# STM32F103RCT6.net
KiCad netlist of a schematic drawn in Altium Designer
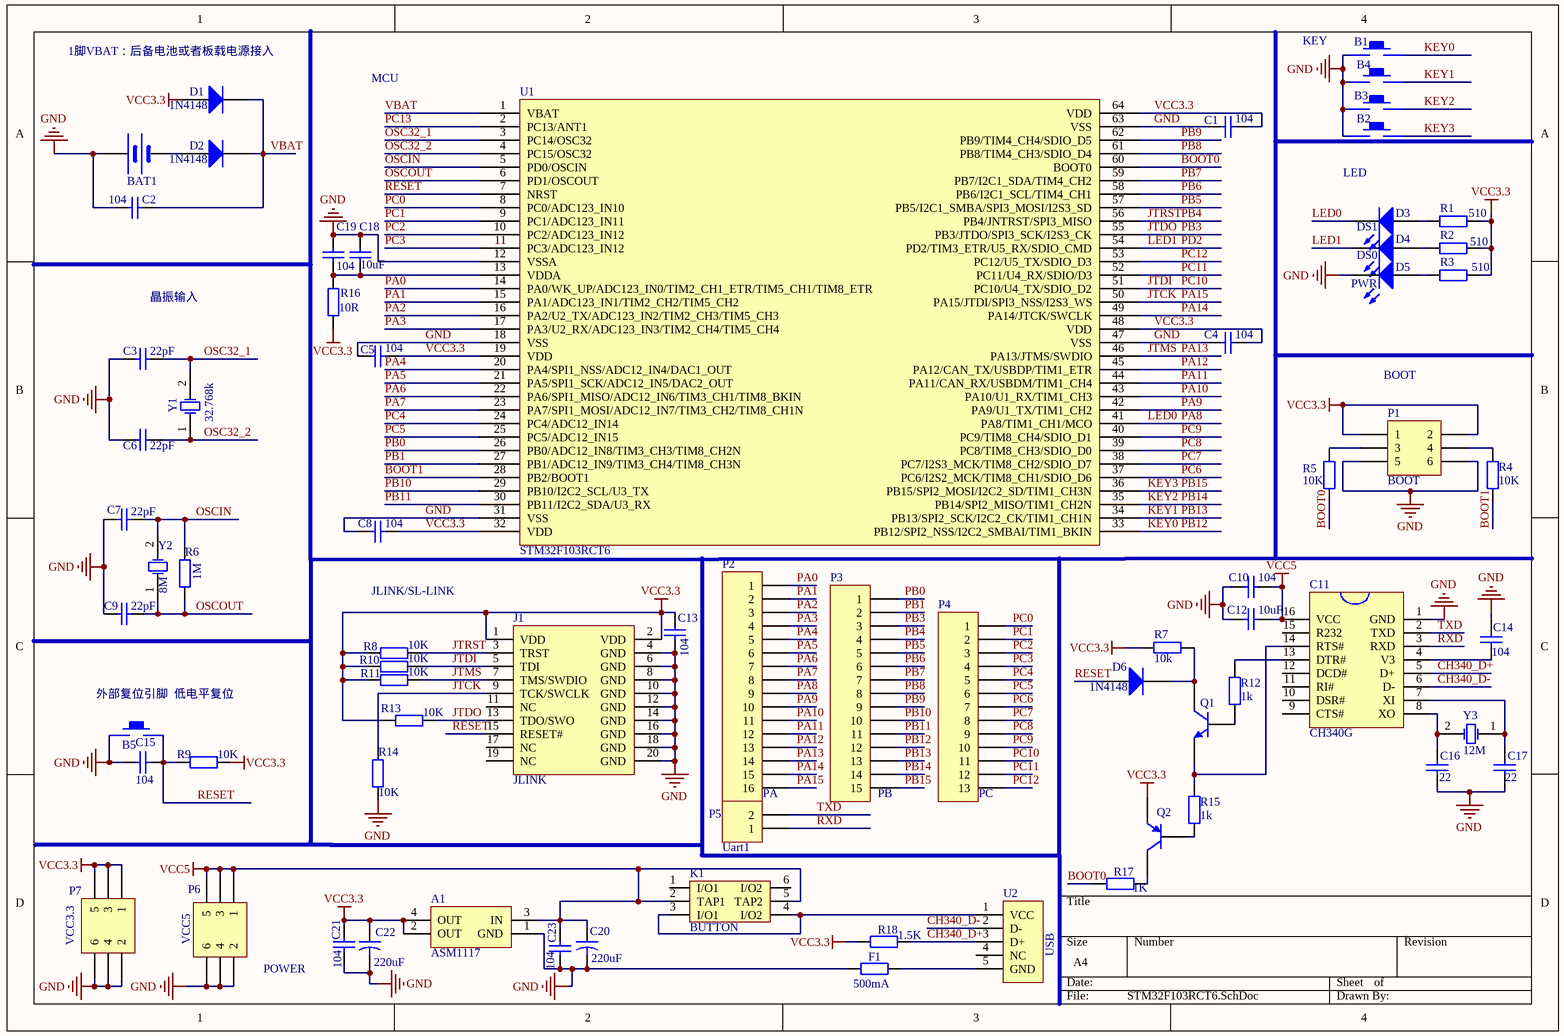
[diagram p0: STM32F103RCT6.SchDoc]

(export (version "E")
  (design (tool "Eeschema 10.0.6"))
  (components
    (comp (ref "A1") (value "ASM1117") (footprint "AMS1117") (libsource (lib "STM32F103") (part "AMS117")))
    (comp (ref "B1") (value "Button") (footprint "KEY_M") (libsource (lib "STM32F103") (part "Button")))
    (comp (ref "B2") (value "Button") (footprint "KEY_M") (libsource (lib "STM32F103") (part "Button")))
    (comp (ref "B3") (value "Button") (footprint "KEY_M") (libsource (lib "STM32F103") (part "Button")))
    (comp (ref "B4") (value "Button") (footprint "KEY_M") (libsource (lib "STM32F103") (part "Button")))
    (comp (ref "B5") (value "Button") (footprint "KEY_M") (libsource (lib "STM32F103") (part "Button")))
    (comp (ref "BAT1") (value "BATT") (footprint "BATM") (libsource (lib "MiniSTM32 V3.0封装库") (part "BAT")))
    (comp (ref "C1")
      (value "104")
      (footprint "0603P")
      (description "Capacitor")
      (fields (field (name "PUBLISHER") "Altium Limited"))
      (libsource (lib "Miscellaneous Devices") (part "Cap"))
    )
    (comp (ref "C2")
      (value "104")
      (footprint "0603P")
      (description "Capacitor")
      (fields (field (name "PUBLISHER") "Altium Limited"))
      (libsource (lib "Miscellaneous Devices") (part "Cap"))
    )
    (comp (ref "C3")
      (value "22pF")
      (footprint "0603P")
      (description "Capacitor")
      (fields (field (name "PUBLISHER") "Altium Limited"))
      (libsource (lib "Miscellaneous Devices") (part "Cap"))
    )
    (comp (ref "C4")
      (value "104")
      (footprint "0603P")
      (description "Capacitor")
      (fields (field (name "PUBLISHER") "Altium Limited"))
      (libsource (lib "Miscellaneous Devices") (part "Cap"))
    )
    (comp (ref "C5")
      (value "104")
      (footprint "0603P")
      (description "Capacitor")
      (fields (field (name "PUBLISHER") "Altium Limited"))
      (libsource (lib "Miscellaneous Devices") (part "Cap"))
    )
    (comp (ref "C6")
      (value "22pF")
      (footprint "0603P")
      (description "Capacitor")
      (fields (field (name "PUBLISHER") "Altium Limited"))
      (libsource (lib "Miscellaneous Devices") (part "Cap"))
    )
    (comp (ref "C7")
      (value "22pF")
      (footprint "0603P")
      (description "Capacitor")
      (fields (field (name "PUBLISHER") "Altium Limited"))
      (libsource (lib "Miscellaneous Devices") (part "Cap"))
    )
    (comp (ref "C8")
      (value "104")
      (footprint "0603P")
      (description "Capacitor")
      (fields (field (name "PUBLISHER") "Altium Limited"))
      (libsource (lib "Miscellaneous Devices") (part "Cap"))
    )
    (comp (ref "C9")
      (value "22pF")
      (footprint "0603P")
      (description "Capacitor")
      (fields (field (name "PUBLISHER") "Altium Limited"))
      (libsource (lib "Miscellaneous Devices") (part "Cap"))
    )
    (comp (ref "C10")
      (value "104")
      (footprint "0603P")
      (description "Capacitor")
      (fields (field (name "PUBLISHER") "Altium Limited"))
      (libsource (lib "Miscellaneous Devices") (part "Cap"))
    )
    (comp (ref "C11") (value "CH340G") (footprint "SOP16M") (libsource (lib "STM32F103") (part "CH340G")))
    (comp (ref "C12")
      (value "10uF")
      (footprint "0805")
      (description "Capacitor")
      (fields (field (name "PUBLISHER") "Altium Limited"))
      (libsource (lib "Miscellaneous Devices") (part "Cap"))
    )
    (comp (ref "C13")
      (value "104")
      (footprint "0603P")
      (description "Capacitor")
      (fields (field (name "PUBLISHER") "Altium Limited"))
      (libsource (lib "Miscellaneous Devices") (part "Cap"))
    )
    (comp (ref "C14")
      (value "104")
      (footprint "0603P")
      (description "Capacitor")
      (fields (field (name "PUBLISHER") "Altium Limited"))
      (libsource (lib "Miscellaneous Devices") (part "Cap"))
    )
    (comp (ref "C15")
      (value "104")
      (footprint "0603P")
      (description "Capacitor")
      (fields (field (name "PUBLISHER") "Altium Limited"))
      (libsource (lib "Miscellaneous Devices") (part "Cap"))
    )
    (comp (ref "C16")
      (value "22")
      (footprint "0603P")
      (description "Capacitor")
      (fields (field (name "PUBLISHER") "Altium Limited"))
      (libsource (lib "Miscellaneous Devices") (part "Cap"))
    )
    (comp (ref "C17")
      (value "22")
      (footprint "0603P")
      (description "Capacitor")
      (fields (field (name "PUBLISHER") "Altium Limited"))
      (libsource (lib "Miscellaneous Devices") (part "Cap"))
    )
    (comp (ref "C18")
      (value "10uF")
      (footprint "0805")
      (description "Capacitor")
      (fields (field (name "PUBLISHER") "Altium Limited"))
      (libsource (lib "Miscellaneous Devices") (part "Cap"))
    )
    (comp (ref "C19")
      (value "104")
      (footprint "0603P")
      (description "Capacitor")
      (fields (field (name "PUBLISHER") "Altium Limited"))
      (libsource (lib "Miscellaneous Devices") (part "Cap"))
    )
    (comp (ref "C20")
      (value "220uF")
      (footprint "CC6.56.5")
      (description "Capacitor")
      (fields (field (name "Comment") "Cap2") (field (name "PUBLISHER") "Altium Limited"))
      (libsource (lib "Miscellaneous Devices") (part "Cap2"))
    )
    (comp (ref "C21")
      (value "104")
      (footprint "0603P")
      (description "Capacitor")
      (fields (field (name "PUBLISHER") "Altium Limited"))
      (libsource (lib "Miscellaneous Devices") (part "Cap"))
    )
    (comp (ref "C22")
      (value "220uF")
      (footprint "CC6.56.5")
      (description "Capacitor")
      (fields (field (name "Comment") "Cap2") (field (name "PUBLISHER") "Altium Limited"))
      (libsource (lib "Miscellaneous Devices") (part "Cap2"))
    )
    (comp (ref "C23")
      (value "104")
      (footprint "0603P")
      (description "Capacitor")
      (fields (field (name "PUBLISHER") "Altium Limited"))
      (libsource (lib "Miscellaneous Devices") (part "Cap"))
    )
    (comp (ref "D1")
      (value "1N4148")
      (footprint "DIODE_SOP")
      (fields (field (name "PUBLISHER") "Altium Limited"))
      (libsource (lib "STM32F103") (part "LED"))
    )
    (comp (ref "D2")
      (value "1N4148")
      (footprint "DIODE_SOP")
      (fields (field (name "PUBLISHER") "Altium Limited"))
      (libsource (lib "STM32F103") (part "LED"))
    )
    (comp (ref "D3")
      (value "DS1")
      (footprint "DIODE_SOP")
      (description "Typical BLUE SiC LED")
      (fields (field (name "PUBLISHER") "Altium Limited"))
      (libsource (lib "Miscellaneous Devices") (part "LED3"))
    )
    (comp (ref "D4")
      (value "DS0")
      (footprint "DIODE_SOP")
      (description "Typical BLUE SiC LED")
      (fields (field (name "PUBLISHER") "Altium Limited"))
      (libsource (lib "Miscellaneous Devices") (part "LED3"))
    )
    (comp (ref "D5")
      (value "PWR")
      (footprint "DIODE_SOP")
      (description "Typical BLUE SiC LED")
      (fields (field (name "PUBLISHER") "Altium Limited"))
      (libsource (lib "Miscellaneous Devices") (part "LED3"))
    )
    (comp (ref "D6")
      (value "1N4148")
      (footprint "DIODE_SOP")
      (fields (field (name "PUBLISHER") "Altium Limited"))
      (libsource (lib "STM32F103") (part "LED"))
    )
    (comp (ref "F1")
      (value "500mA")
      (footprint "0805")
      (description "Resistor")
      (fields (field (name "PUBLISHER") "Altium Limited"))
      (libsource (lib "") (part "Res2_1"))
    )
    (comp (ref "J1")
      (value "JLINK")
      (footprint "JTAG_20")
      (fields (field (name "PUBLISHER") "Altium Limited"))
      (libsource (lib "STM32F103") (part "JLINK2X10"))
    )
    (comp (ref "K1")
      (value "BUTTON")
      (footprint "BTN8.5*8.5")
      (libsource (lib "MiniSTM32 V3.0封装库") (part "BUTTON"))
    )
    (comp (ref "P1")
      (value "BOOT")
      (footprint "HDR2X3")
      (description "Header, 3-Pin, Dual row")
      (fields (field (name "PUBLISHER") "Altium Limited"))
      (libsource (lib "Miscellaneous Connectors") (part "Header 3X2"))
    )
    (comp (ref "P2")
      (value "PA")
      (footprint "HDR1X16")
      (description "Header, 16-Pin")
      (fields (field (name "PUBLISHER") "Altium Limited"))
      (libsource (lib "Miscellaneous Connectors") (part "Header 16"))
    )
    (comp (ref "P3")
      (value "PB")
      (footprint "HDR1X15")
      (description "Header, 15-Pin")
      (fields (field (name "PUBLISHER") "Altium Limited"))
      (libsource (lib "Miscellaneous Connectors") (part "Header 15"))
    )
    (comp (ref "P4")
      (value "PC")
      (footprint "HDR1X13")
      (description "Header, 13-Pin")
      (fields (field (name "PUBLISHER") "Altium Limited"))
      (libsource (lib "Miscellaneous Connectors") (part "Header 13"))
    )
    (comp (ref "P5")
      (value "Uart1")
      (footprint "HDR1X2")
      (description "Header, 2-Pin")
      (fields (field (name "PUBLISHER") "Altium Limited"))
      (libsource (lib "Miscellaneous Connectors") (part "Header 2"))
    )
    (comp (ref "P6")
      (value "VCC5")
      (footprint "HDR2X3")
      (description "Header, 3-Pin, Dual row")
      (fields (field (name "PUBLISHER") "Altium Limited"))
      (libsource (lib "") (part "Header 3X2_1"))
    )
    (comp (ref "P7")
      (value "VCC3.3")
      (footprint "HDR2X3")
      (description "Header, 3-Pin, Dual row")
      (fields (field (name "PUBLISHER") "Altium Limited"))
      (libsource (lib "") (part "Header 3X2_1"))
    )
    (comp (ref "Q1")
      (value "2N3904")
      (footprint "SOT-23R")
      (description "NPN General Purpose Amplifier")
      (fields (field (name "PUBLISHER") "Altium Limited"))
      (libsource (lib "Miscellaneous Devices") (part "2N3904"))
    )
    (comp (ref "Q2")
      (value "2N3906")
      (footprint "SOT-23R")
      (description "PNP General Purpose Amplifier")
      (fields (field (name "PUBLISHER") "Altium Limited"))
      (libsource (lib "Miscellaneous Devices") (part "2N3906"))
    )
    (comp (ref "R1")
      (value "510")
      (footprint "0603P")
      (description "Resistor")
      (fields (field (name "Comment") "Res2") (field (name "PUBLISHER") "Altium Limited"))
      (libsource (lib "") (part "Res2_3"))
    )
    (comp (ref "R2")
      (value "510")
      (footprint "0603P")
      (description "Resistor")
      (fields (field (name "Comment") "Res2") (field (name "PUBLISHER") "Altium Limited"))
      (libsource (lib "") (part "Res2_3"))
    )
    (comp (ref "R3")
      (value "510")
      (footprint "0603P")
      (description "Resistor")
      (fields (field (name "Comment") "Res2") (field (name "PUBLISHER") "Altium Limited"))
      (libsource (lib "") (part "Res2_3"))
    )
    (comp (ref "R4")
      (value "10K")
      (footprint "0603P")
      (description "Resistor")
      (fields (field (name "Comment") "Res2") (field (name "PUBLISHER") "Altium Limited"))
      (libsource (lib "Miscellaneous Devices") (part "Res2"))
    )
    (comp (ref "R5")
      (value "10K")
      (footprint "0603P")
      (description "Resistor")
      (fields (field (name "Comment") "Res2") (field (name "PUBLISHER") "Altium Limited"))
      (libsource (lib "Miscellaneous Devices") (part "Res2"))
    )
    (comp (ref "R6")
      (value "1M")
      (footprint "0603P")
      (description "Resistor")
      (fields (field (name "Comment") "Res2") (field (name "PUBLISHER") "Altium Limited"))
      (libsource (lib "Miscellaneous Devices") (part "Res2"))
    )
    (comp (ref "R7")
      (value "10k")
      (footprint "0603P")
      (description "Resistor")
      (fields (field (name "Comment") "Res2") (field (name "PUBLISHER") "Altium Limited"))
      (libsource (lib "") (part "Res2_1"))
    )
    (comp (ref "R8")
      (value "10K")
      (footprint "0603P")
      (description "Resistor")
      (fields (field (name "Comment") "Res2") (field (name "PUBLISHER") "Altium Limited"))
      (libsource (lib "") (part "Res2_1"))
    )
    (comp (ref "R9")
      (value "10K")
      (footprint "0603P")
      (description "Resistor")
      (fields (field (name "Comment") "Res2") (field (name "PUBLISHER") "Altium Limited"))
      (libsource (lib "") (part "Res2_1"))
    )
    (comp (ref "R10")
      (value "10K")
      (footprint "0603P")
      (description "Resistor")
      (fields (field (name "Comment") "Res2") (field (name "PUBLISHER") "Altium Limited"))
      (libsource (lib "") (part "Res2_1"))
    )
    (comp (ref "R11")
      (value "10K")
      (footprint "0603P")
      (description "Resistor")
      (fields (field (name "Comment") "Res2") (field (name "PUBLISHER") "Altium Limited"))
      (libsource (lib "") (part "Res2_1"))
    )
    (comp (ref "R12")
      (value "1k")
      (footprint "0603P")
      (description "Resistor")
      (fields (field (name "Comment") "Res2") (field (name "PUBLISHER") "Altium Limited"))
      (libsource (lib "Miscellaneous Devices") (part "Res2"))
    )
    (comp (ref "R13")
      (value "10K")
      (footprint "0603P")
      (description "Resistor")
      (fields (field (name "Comment") "Res2") (field (name "PUBLISHER") "Altium Limited"))
      (libsource (lib "") (part "Res2_1"))
    )
    (comp (ref "R14")
      (value "10K")
      (footprint "0603P")
      (description "Resistor")
      (fields (field (name "Comment") "Res2") (field (name "PUBLISHER") "Altium Limited"))
      (libsource (lib "Miscellaneous Devices") (part "Res2"))
    )
    (comp (ref "R15")
      (value "1k")
      (footprint "0603P")
      (description "Resistor")
      (fields (field (name "Comment") "Res2") (field (name "PUBLISHER") "Altium Limited"))
      (libsource (lib "") (part "Res2_2"))
    )
    (comp (ref "R16")
      (value "10R")
      (footprint "0603P")
      (description "Resistor")
      (fields (field (name "Comment") "Res2") (field (name "PUBLISHER") "Altium Limited"))
      (libsource (lib "") (part "Res2_2"))
    )
    (comp (ref "R17")
      (value "1K")
      (footprint "0603P")
      (description "Resistor")
      (fields (field (name "Comment") "Res2") (field (name "PUBLISHER") "Altium Limited"))
      (libsource (lib "") (part "Res2_1"))
    )
    (comp (ref "R18")
      (value "1.5K")
      (footprint "0603P")
      (description "Resistor")
      (fields (field (name "Comment") "Res2") (field (name "PUBLISHER") "Altium Limited"))
      (libsource (lib "") (part "Res2_1"))
    )
    (comp (ref "U1")
      (value "STM32F103RCT6")
      (footprint "LQFP64")
      (libsource (lib "STM32F103") (part "STM32F103RCT6_64Pin"))
    )
    (comp (ref "U2") (value "USB") (footprint "USB/SM0.8-6H5") (libsource (lib "STM32F103") (part "USB")))
    (comp (ref "Y1")
      (value "32.768k")
      (footprint "XTAL32")
      (description "Crystal Oscillator")
      (fields (field (name "PUBLISHER") "Altium Limited"))
      (libsource (lib "Miscellaneous Devices") (part "XTAL"))
    )
    (comp (ref "Y2")
      (value "8M")
      (footprint "XTAL_US")
      (description "Crystal Oscillator")
      (fields (field (name "PUBLISHER") "Altium Limited"))
      (libsource (lib "Miscellaneous Devices") (part "XTAL"))
    )
    (comp (ref "Y3")
      (value "12M")
      (footprint "XTAL_US")
      (description "Crystal Oscillator")
      (fields (field (name "PUBLISHER") "Altium Limited"))
      (libsource (lib "Miscellaneous Devices") (part "XTAL"))
    )
  )
  (nets
    (net (code "1") (name "/BOOT0") (class "Default")
      (node (ref "R17") (pin "1") (pinfunction "1_1") (pintype "passive"))
      (node (ref "R5") (pin "1") (pinfunction "1_1") (pintype "passive"))
      (node (ref "U1") (pin "60") (pinfunction "BOOT0_60") (pintype "passive"))
    )
    (net (code "2") (name "/BOOT1") (class "Default")
      (node (ref "R4") (pin "1") (pinfunction "1_1") (pintype "passive"))
      (node (ref "U1") (pin "28") (pinfunction "PB2/BOOT1_28") (pintype "passive"))
    )
    (net (code "3") (name "/CH340_D+") (class "Default")
      (node (ref "C11") (pin "5") (pinfunction "D+_5") (pintype "passive"))
      (node (ref "R18") (pin "2") (pinfunction "2_2") (pintype "passive"))
      (node (ref "U2") (pin "3") (pinfunction "D+_3") (pintype "passive"))
    )
    (net (code "4") (name "/CH340_D-") (class "Default")
      (node (ref "C11") (pin "6") (pinfunction "D-_6") (pintype "passive"))
      (node (ref "U2") (pin "2") (pinfunction "D-_2") (pintype "passive"))
    )
    (net (code "5") (name "/JTCK") (class "Default")
      (node (ref "J1") (pin "9") (pinfunction "TCK/SWCLK_9") (pintype "passive"))
      (node (ref "P2") (pin "16") (pinfunction "16_16") (pintype "passive"))
      (node (ref "R14") (pin "2") (pinfunction "2_2") (pintype "passive"))
      (node (ref "U1") (pin "50") (pinfunction "PA15/JTDI/SPI3_NSS/I2S3_WS_50") (pintype "passive"))
    )
    (net (code "6") (name "/JTDI") (class "Default")
      (node (ref "J1") (pin "5") (pinfunction "TDI_5") (pintype "passive"))
      (node (ref "P4") (pin "11") (pinfunction "11_11") (pintype "passive"))
      (node (ref "R10") (pin "2") (pinfunction "2_2") (pintype "passive"))
      (node (ref "U1") (pin "51") (pinfunction "PC10/U4_TX/SDIO_D2_51") (pintype "passive"))
    )
    (net (code "7") (name "/JTDO") (class "Default")
      (node (ref "J1") (pin "13") (pinfunction "TDO/SWO_13") (pintype "passive"))
      (node (ref "P3") (pin "3") (pinfunction "3_3") (pintype "passive"))
      (node (ref "R13") (pin "2") (pinfunction "2_2") (pintype "passive"))
      (node (ref "U1") (pin "55") (pinfunction "PB3/JTDO/SPI3_SCK/I2S3_CK_55") (pintype "passive"))
    )
    (net (code "8") (name "/JTMS") (class "Default")
      (node (ref "J1") (pin "7") (pinfunction "TMS/SWDIO_7") (pintype "passive"))
      (node (ref "P2") (pin "14") (pinfunction "14_14") (pintype "passive"))
      (node (ref "R11") (pin "2") (pinfunction "2_2") (pintype "passive"))
      (node (ref "U1") (pin "46") (pinfunction "PA13/JTMS/SWDIO_46") (pintype "passive"))
    )
    (net (code "9") (name "/JTRST") (class "Default")
      (node (ref "J1") (pin "3") (pinfunction "TRST_3") (pintype "passive"))
      (node (ref "P3") (pin "4") (pinfunction "4_4") (pintype "passive"))
      (node (ref "R8") (pin "2") (pinfunction "2_2") (pintype "passive"))
      (node (ref "U1") (pin "56") (pinfunction "PB4/JNTRST/SPI3_MISO_56") (pintype "passive"))
    )
    (net (code "10") (name "/KEY0") (class "Default")
      (node (ref "B1") (pin "2") (pinfunction "68_2") (pintype "passive"))
      (node (ref "P3") (pin "12") (pinfunction "12_12") (pintype "passive"))
      (node (ref "U1") (pin "33") (pinfunction "PB12/SPI2_NSS/I2C2_SMBAI/TIM1_BKIN_33") (pintype "passive"))
    )
    (net (code "11") (name "/KEY1") (class "Default")
      (node (ref "B4") (pin "2") (pinfunction "68_2") (pintype "passive"))
      (node (ref "P3") (pin "13") (pinfunction "13_13") (pintype "passive"))
      (node (ref "U1") (pin "34") (pinfunction "PB13/SPI2_SCK/I2C2_CK/TIM1_CH1N_34") (pintype "passive"))
    )
    (net (code "12") (name "/KEY2") (class "Default")
      (node (ref "B3") (pin "2") (pinfunction "68_2") (pintype "passive"))
      (node (ref "P3") (pin "14") (pinfunction "14_14") (pintype "passive"))
      (node (ref "U1") (pin "35") (pinfunction "PB14/SPI2_MISO/TIM1_CH2N_35") (pintype "passive"))
    )
    (net (code "13") (name "/KEY3") (class "Default")
      (node (ref "B2") (pin "2") (pinfunction "68_2") (pintype "passive"))
      (node (ref "P3") (pin "15") (pinfunction "15_15") (pintype "passive"))
      (node (ref "U1") (pin "36") (pinfunction "PB15/SPI2_MOSI/I2C2_SD/TIM1_CH3N_36") (pintype "passive"))
    )
    (net (code "14") (name "/LED0") (class "Default")
      (node (ref "D3") (pin "2") (pinfunction "K_2") (pintype "passive"))
      (node (ref "P2") (pin "9") (pinfunction "9_9") (pintype "passive"))
      (node (ref "U1") (pin "41") (pinfunction "PA8/TIM1_CH1/MCO_41") (pintype "passive"))
    )
    (net (code "15") (name "/LED1") (class "Default")
      (node (ref "D4") (pin "2") (pinfunction "K_2") (pintype "passive"))
      (node (ref "U1") (pin "54") (pinfunction "PD2/TIM3_ETR/U5_RX/SDIO_CMD_54") (pintype "passive"))
    )
    (net (code "16") (name "/OSC32_1") (class "Default")
      (node (ref "C3") (pin "2") (pinfunction "2_2") (pintype "passive"))
      (node (ref "U1") (pin "3") (pinfunction "PC14/OSC32_3") (pintype "passive"))
      (node (ref "Y1") (pin "2") (pinfunction "OSC2_2") (pintype "passive"))
    )
    (net (code "17") (name "/OSC32_2") (class "Default")
      (node (ref "C6") (pin "2") (pinfunction "2_2") (pintype "passive"))
      (node (ref "U1") (pin "4") (pinfunction "PC15/OSC32_4") (pintype "passive"))
      (node (ref "Y1") (pin "1") (pinfunction "OSC1_1") (pintype "passive"))
    )
    (net (code "18") (name "/OSCIN") (class "Default")
      (node (ref "C7") (pin "2") (pinfunction "2_2") (pintype "passive"))
      (node (ref "R6") (pin "2") (pinfunction "2_2") (pintype "passive"))
      (node (ref "U1") (pin "5") (pinfunction "PD0/OSCIN_5") (pintype "passive"))
      (node (ref "Y2") (pin "2") (pinfunction "OSC2_2") (pintype "passive"))
    )
    (net (code "19") (name "/OSCOUT") (class "Default")
      (node (ref "C9") (pin "2") (pinfunction "2_2") (pintype "passive"))
      (node (ref "R6") (pin "1") (pinfunction "1_1") (pintype "passive"))
      (node (ref "U1") (pin "6") (pinfunction "PD1/OSCOUT_6") (pintype "passive"))
      (node (ref "Y2") (pin "1") (pinfunction "OSC1_1") (pintype "passive"))
    )
    (net (code "20") (name "/PA0") (class "Default")
      (node (ref "P2") (pin "1") (pinfunction "1_1") (pintype "passive"))
      (node (ref "U1") (pin "14") (pinfunction "PA0/WK_UP/ADC123_IN0/TIM2_CH1_ETR/TIM5_CH1/TIM8_ETR_14") (pintype "passive"))
    )
    (net (code "21") (name "/PA1") (class "Default")
      (node (ref "P2") (pin "2") (pinfunction "2_2") (pintype "passive"))
      (node (ref "U1") (pin "15") (pinfunction "PA1/ADC123_IN1/TIM2_CH2/TIM5_CH2_15") (pintype "passive"))
    )
    (net (code "22") (name "/PA2") (class "Default")
      (node (ref "P2") (pin "3") (pinfunction "3_3") (pintype "passive"))
      (node (ref "U1") (pin "16") (pinfunction "PA2/U2_TX/ADC123_IN2/TIM2_CH3/TIM5_CH3_16") (pintype "passive"))
    )
    (net (code "23") (name "/PA3") (class "Default")
      (node (ref "P2") (pin "4") (pinfunction "4_4") (pintype "passive"))
      (node (ref "U1") (pin "17") (pinfunction "PA3/U2_RX/ADC123_IN3/TIM2_CH4/TIM5_CH4_17") (pintype "passive"))
    )
    (net (code "24") (name "/PA4") (class "Default")
      (node (ref "P2") (pin "5") (pinfunction "5_5") (pintype "passive"))
      (node (ref "U1") (pin "20") (pinfunction "PA4/SPI1_NSS/ADC12_IN4/DAC1_OUT_20") (pintype "passive"))
    )
    (net (code "25") (name "/PA5") (class "Default")
      (node (ref "P2") (pin "6") (pinfunction "6_6") (pintype "passive"))
      (node (ref "U1") (pin "21") (pinfunction "PA5/SPI1_SCK/ADC12_IN5/DAC2_OUT_21") (pintype "passive"))
    )
    (net (code "26") (name "/PA6") (class "Default")
      (node (ref "P2") (pin "7") (pinfunction "7_7") (pintype "passive"))
      (node (ref "U1") (pin "22") (pinfunction "PA6/SPI1_MISO/ADC12_IN6/TIM3_CH1/TIM8_BKIN_22") (pintype "passive"))
    )
    (net (code "27") (name "/PA7") (class "Default")
      (node (ref "P2") (pin "8") (pinfunction "8_8") (pintype "passive"))
      (node (ref "U1") (pin "23") (pinfunction "PA7/SPI1_MOSI/ADC12_IN7/TIM3_CH2/TIM8_CH1N_23") (pintype "passive"))
    )
    (net (code "28") (name "/PA9") (class "Default")
      (node (ref "P2") (pin "10") (pinfunction "10_10") (pintype "passive"))
      (node (ref "U1") (pin "42") (pinfunction "PA9/U1_TX/TIM1_CH2_42") (pintype "passive"))
    )
    (net (code "29") (name "/PA10") (class "Default")
      (node (ref "P2") (pin "11") (pinfunction "11_11") (pintype "passive"))
      (node (ref "U1") (pin "43") (pinfunction "PA10/U1_RX/TIM1_CH3_43") (pintype "passive"))
    )
    (net (code "30") (name "/PA11") (class "Default")
      (node (ref "P2") (pin "12") (pinfunction "12_12") (pintype "passive"))
      (node (ref "U1") (pin "44") (pinfunction "PA11/CAN_RX/USBDM/TIM1_CH4_44") (pintype "passive"))
    )
    (net (code "31") (name "/PA12") (class "Default")
      (node (ref "P2") (pin "13") (pinfunction "13_13") (pintype "passive"))
      (node (ref "U1") (pin "45") (pinfunction "PA12/CAN_TX/USBDP/TIM1_ETR_45") (pintype "passive"))
    )
    (net (code "32") (name "/PA14") (class "Default")
      (node (ref "P2") (pin "15") (pinfunction "15_15") (pintype "passive"))
      (node (ref "U1") (pin "49") (pinfunction "PA14/JTCK/SWCLK_49") (pintype "passive"))
    )
    (net (code "33") (name "/PB0") (class "Default")
      (node (ref "P3") (pin "1") (pinfunction "1_1") (pintype "passive"))
      (node (ref "U1") (pin "26") (pinfunction "PB0/ADC12_IN8/TIM3_CH3/TIM8_CH2N_26") (pintype "passive"))
    )
    (net (code "34") (name "/PB1") (class "Default")
      (node (ref "P3") (pin "2") (pinfunction "2_2") (pintype "passive"))
      (node (ref "U1") (pin "27") (pinfunction "PB1/ADC12_IN9/TIM3_CH4/TIM8_CH3N_27") (pintype "passive"))
    )
    (net (code "35") (name "/PB5") (class "Default")
      (node (ref "P3") (pin "5") (pinfunction "5_5") (pintype "passive"))
      (node (ref "U1") (pin "57") (pinfunction "PB5/I2C1_SMBA/SPI3_MOSI/I2S3_SD_57") (pintype "passive"))
    )
    (net (code "36") (name "/PB6") (class "Default")
      (node (ref "P3") (pin "6") (pinfunction "6_6") (pintype "passive"))
      (node (ref "U1") (pin "58") (pinfunction "PB6/I2C1_SCL/TIM4_CH1_58") (pintype "passive"))
    )
    (net (code "37") (name "/PB7") (class "Default")
      (node (ref "P3") (pin "7") (pinfunction "7_7") (pintype "passive"))
      (node (ref "U1") (pin "59") (pinfunction "PB7/I2C1_SDA/TIM4_CH2_59") (pintype "passive"))
    )
    (net (code "38") (name "/PB8") (class "Default")
      (node (ref "P3") (pin "8") (pinfunction "8_8") (pintype "passive"))
      (node (ref "U1") (pin "61") (pinfunction "PB8/TIM4_CH3/SDIO_D4_61") (pintype "passive"))
    )
    (net (code "39") (name "/PB9") (class "Default")
      (node (ref "P3") (pin "9") (pinfunction "9_9") (pintype "passive"))
      (node (ref "U1") (pin "62") (pinfunction "PB9/TIM4_CH4/SDIO_D5_62") (pintype "passive"))
    )
    (net (code "40") (name "/PB10") (class "Default")
      (node (ref "P3") (pin "10") (pinfunction "10_10") (pintype "passive"))
      (node (ref "U1") (pin "29") (pinfunction "PB10/I2C2_SCL/U3_TX_29") (pintype "passive"))
    )
    (net (code "41") (name "/PB11") (class "Default")
      (node (ref "P3") (pin "11") (pinfunction "11_11") (pintype "passive"))
      (node (ref "U1") (pin "30") (pinfunction "PB11/I2C2_SDA/U3_RX_30") (pintype "passive"))
    )
    (net (code "42") (name "/PC0") (class "Default")
      (node (ref "P4") (pin "1") (pinfunction "1_1") (pintype "passive"))
      (node (ref "U1") (pin "8") (pinfunction "PC0/ADC123_IN10_8") (pintype "passive"))
    )
    (net (code "43") (name "/PC1") (class "Default")
      (node (ref "P4") (pin "2") (pinfunction "2_2") (pintype "passive"))
      (node (ref "U1") (pin "9") (pinfunction "PC1/ADC123_IN11_9") (pintype "passive"))
    )
    (net (code "44") (name "/PC2") (class "Default")
      (node (ref "P4") (pin "3") (pinfunction "3_3") (pintype "passive"))
      (node (ref "U1") (pin "10") (pinfunction "PC2/ADC123_IN12_10") (pintype "passive"))
    )
    (net (code "45") (name "/PC3") (class "Default")
      (node (ref "P4") (pin "4") (pinfunction "4_4") (pintype "passive"))
      (node (ref "U1") (pin "11") (pinfunction "PC3/ADC123_IN12_11") (pintype "passive"))
    )
    (net (code "46") (name "/PC4") (class "Default")
      (node (ref "P4") (pin "5") (pinfunction "5_5") (pintype "passive"))
      (node (ref "U1") (pin "24") (pinfunction "PC4/ADC12_IN14_24") (pintype "passive"))
    )
    (net (code "47") (name "/PC5") (class "Default")
      (node (ref "P4") (pin "6") (pinfunction "6_6") (pintype "passive"))
      (node (ref "U1") (pin "25") (pinfunction "PC5/ADC12_IN15_25") (pintype "passive"))
    )
    (net (code "48") (name "/PC6") (class "Default")
      (node (ref "P4") (pin "7") (pinfunction "7_7") (pintype "passive"))
      (node (ref "U1") (pin "37") (pinfunction "PC6/I2S2_MCK/TIM8_CH1/SDIO_D6_37") (pintype "passive"))
    )
    (net (code "49") (name "/PC7") (class "Default")
      (node (ref "P4") (pin "8") (pinfunction "8_8") (pintype "passive"))
      (node (ref "U1") (pin "38") (pinfunction "PC7/I2S3_MCK/TIM8_CH2/SDIO_D7_38") (pintype "passive"))
    )
    (net (code "50") (name "/PC8") (class "Default")
      (node (ref "P4") (pin "9") (pinfunction "9_9") (pintype "passive"))
      (node (ref "U1") (pin "39") (pinfunction "PC8/TIM8_CH3/SDIO_D0_39") (pintype "passive"))
    )
    (net (code "51") (name "/PC9") (class "Default")
      (node (ref "P4") (pin "10") (pinfunction "10_10") (pintype "passive"))
      (node (ref "U1") (pin "40") (pinfunction "PC9/TIM8_CH4/SDIO_D1_40") (pintype "passive"))
    )
    (net (code "52") (name "/PC11") (class "Default")
      (node (ref "P4") (pin "12") (pinfunction "12_12") (pintype "passive"))
      (node (ref "U1") (pin "52") (pinfunction "PC11/U4_RX/SDIO/D3_52") (pintype "passive"))
    )
    (net (code "53") (name "/PC12") (class "Default")
      (node (ref "P4") (pin "13") (pinfunction "13_13") (pintype "passive"))
      (node (ref "U1") (pin "53") (pinfunction "PC12/U5_TX/SDIO_D3_53") (pintype "passive"))
    )
    (net (code "54") (name "/PC13") (class "Default")
      (node (ref "U1") (pin "2") (pinfunction "PC13/ANT1_2") (pintype "passive"))
    )
    (net (code "55") (name "/RESET") (class "Default")
      (node (ref "B5") (pin "2") (pinfunction "68_2") (pintype "passive"))
      (node (ref "C15") (pin "1") (pinfunction "1_1") (pintype "passive"))
      (node (ref "D6") (pin "1") (pinfunction "A_1") (pintype "passive"))
      (node (ref "J1") (pin "15") (pinfunction "RESET#_15") (pintype "passive"))
      (node (ref "R9") (pin "1") (pinfunction "1_1") (pintype "passive"))
      (node (ref "U1") (pin "7") (pinfunction "NRST_7") (pintype "passive"))
    )
    (net (code "56") (name "/RXD") (class "Default")
      (node (ref "C11") (pin "3") (pinfunction "RXD_3") (pintype "passive"))
      (node (ref "P5") (pin "1") (pinfunction "1_1") (pintype "passive"))
    )
    (net (code "57") (name "/TXD") (class "Default")
      (node (ref "C11") (pin "2") (pinfunction "TXD_2") (pintype "passive"))
      (node (ref "P5") (pin "2") (pinfunction "2_2") (pintype "passive"))
    )
    (net (code "58") (name "/VBAT") (class "Default")
      (node (ref "C2") (pin "2") (pinfunction "2_2") (pintype "passive"))
      (node (ref "D1") (pin "2") (pinfunction "K_2") (pintype "passive"))
      (node (ref "D2") (pin "2") (pinfunction "K_2") (pintype "passive"))
      (node (ref "U1") (pin "1") (pinfunction "VBAT_1") (pintype "passive"))
    )
    (net (code "59") (name "GND") (class "Default")
      (node (ref "A1") (pin "1") (pinfunction "GND_1") (pintype "passive"))
      (node (ref "B1") (pin "1") (pinfunction "67_1") (pintype "passive"))
      (node (ref "B2") (pin "1") (pinfunction "67_1") (pintype "passive"))
      (node (ref "B3") (pin "1") (pinfunction "67_1") (pintype "passive"))
      (node (ref "B4") (pin "1") (pinfunction "67_1") (pintype "passive"))
      (node (ref "B5") (pin "1") (pinfunction "67_1") (pintype "passive"))
      (node (ref "BAT1") (pin "1") (pinfunction "VCC_1") (pintype "passive"))
      (node (ref "C1") (pin "2") (pinfunction "2_2") (pintype "passive"))
      (node (ref "C10") (pin "1") (pinfunction "1_1") (pintype "passive"))
      (node (ref "C11") (pin "1") (pinfunction "GND_1") (pintype "passive"))
      (node (ref "C12") (pin "1") (pinfunction "1_1") (pintype "passive"))
      (node (ref "C13") (pin "2") (pinfunction "2_2") (pintype "passive"))
      (node (ref "C14") (pin "1") (pinfunction "1_1") (pintype "passive"))
      (node (ref "C15") (pin "2") (pinfunction "2_2") (pintype "passive"))
      (node (ref "C16") (pin "1") (pinfunction "1_1") (pintype "passive"))
      (node (ref "C17") (pin "1") (pinfunction "1_1") (pintype "passive"))
      (node (ref "C18") (pin "1") (pinfunction "1_1") (pintype "passive"))
      (node (ref "C19") (pin "1") (pinfunction "1_1") (pintype "passive"))
      (node (ref "C2") (pin "1") (pinfunction "1_1") (pintype "passive"))
      (node (ref "C20") (pin "2") (pinfunction "2_2") (pintype "passive"))
      (node (ref "C21") (pin "1") (pinfunction "1_1") (pintype "passive"))
      (node (ref "C22") (pin "2") (pinfunction "2_2") (pintype "passive"))
      (node (ref "C23") (pin "1") (pinfunction "1_1") (pintype "passive"))
      (node (ref "C3") (pin "1") (pinfunction "1_1") (pintype "passive"))
      (node (ref "C4") (pin "2") (pinfunction "2_2") (pintype "passive"))
      (node (ref "C5") (pin "2") (pinfunction "2_2") (pintype "passive"))
      (node (ref "C6") (pin "1") (pinfunction "1_1") (pintype "passive"))
      (node (ref "C7") (pin "1") (pinfunction "1_1") (pintype "passive"))
      (node (ref "C8") (pin "2") (pinfunction "2_2") (pintype "passive"))
      (node (ref "C9") (pin "1") (pinfunction "1_1") (pintype "passive"))
      (node (ref "D5") (pin "2") (pinfunction "K_2") (pintype "passive"))
      (node (ref "F1") (pin "1") (pinfunction "1_1") (pintype "passive"))
      (node (ref "J1") (pin "10") (pinfunction "GND_10") (pintype "passive"))
      (node (ref "J1") (pin "12") (pinfunction "GND_12") (pintype "passive"))
      (node (ref "J1") (pin "14") (pinfunction "GND_14") (pintype "passive"))
      (node (ref "J1") (pin "16") (pinfunction "GND_16") (pintype "passive"))
      (node (ref "J1") (pin "18") (pinfunction "GND_18") (pintype "passive"))
      (node (ref "J1") (pin "20") (pinfunction "GND_20") (pintype "passive"))
      (node (ref "J1") (pin "4") (pinfunction "GND_4") (pintype "passive"))
      (node (ref "J1") (pin "6") (pinfunction "GND_6") (pintype "passive"))
      (node (ref "J1") (pin "8") (pinfunction "GND_8") (pintype "passive"))
      (node (ref "P1") (pin "5") (pinfunction "5_5") (pintype "passive"))
      (node (ref "P1") (pin "6") (pinfunction "6_6") (pintype "passive"))
      (node (ref "P6") (pin "2") (pinfunction "2_2") (pintype "passive"))
      (node (ref "P6") (pin "4") (pinfunction "4_4") (pintype "passive"))
      (node (ref "P6") (pin "6") (pinfunction "6_6") (pintype "passive"))
      (node (ref "P7") (pin "2") (pinfunction "2_2") (pintype "passive"))
      (node (ref "P7") (pin "4") (pinfunction "4_4") (pintype "passive"))
      (node (ref "P7") (pin "6") (pinfunction "6_6") (pintype "passive"))
      (node (ref "R14") (pin "1") (pinfunction "1_1") (pintype "passive"))
      (node (ref "U1") (pin "12") (pinfunction "VSSA_12") (pintype "passive"))
      (node (ref "U1") (pin "18") (pinfunction "VSS_18") (pintype "passive"))
      (node (ref "U1") (pin "31") (pinfunction "VSS_31") (pintype "passive"))
      (node (ref "U1") (pin "47") (pinfunction "VSS_47") (pintype "passive"))
      (node (ref "U1") (pin "63") (pinfunction "VSS_63") (pintype "passive"))
    )
    (net (code "60") (name "Net-(BAT1-GND)") (class "Default")
      (node (ref "BAT1") (pin "2") (pinfunction "GND_2") (pintype "passive"))
      (node (ref "D2") (pin "1") (pinfunction "A_1") (pintype "passive"))
    )
    (net (code "61") (name "Net-(C11-DTR#)") (class "Default")
      (node (ref "C11") (pin "13") (pinfunction "DTR#_13") (pintype "passive"))
      (node (ref "R12") (pin "2") (pinfunction "2_2") (pintype "passive"))
    )
    (net (code "62") (name "Net-(C11-RTS#)") (class "Default")
      (node (ref "C11") (pin "14") (pinfunction "RTS#_14") (pintype "passive"))
      (node (ref "Q1") (pin "1") (pinfunction "E_1") (pintype "passive"))
      (node (ref "R15") (pin "1") (pinfunction "1_1") (pintype "passive"))
    )
    (net (code "63") (name "Net-(C11-V3)") (class "Default")
      (node (ref "C11") (pin "4") (pinfunction "V3_4") (pintype "passive"))
      (node (ref "C14") (pin "2") (pinfunction "2_2") (pintype "passive"))
    )
    (net (code "64") (name "Net-(C11-XI)") (class "Default")
      (node (ref "C11") (pin "7") (pinfunction "XI_7") (pintype "passive"))
      (node (ref "C17") (pin "2") (pinfunction "2_2") (pintype "passive"))
      (node (ref "Y3") (pin "1") (pinfunction "OSC1_1") (pintype "passive"))
    )
    (net (code "65") (name "Net-(C11-XO)") (class "Default")
      (node (ref "C11") (pin "8") (pinfunction "XO_8") (pintype "passive"))
      (node (ref "C16") (pin "2") (pinfunction "2_2") (pintype "passive"))
      (node (ref "Y3") (pin "2") (pinfunction "OSC2_2") (pintype "passive"))
    )
    (net (code "66") (name "Net-(D3-A)") (class "Default")
      (node (ref "D3") (pin "1") (pinfunction "A_1") (pintype "passive"))
      (node (ref "R1") (pin "2") (pinfunction "2_2") (pintype "passive"))
    )
    (net (code "67") (name "Net-(D4-A)") (class "Default")
      (node (ref "D4") (pin "1") (pinfunction "A_1") (pintype "passive"))
      (node (ref "R2") (pin "2") (pinfunction "2_2") (pintype "passive"))
    )
    (net (code "68") (name "Net-(D5-A)") (class "Default")
      (node (ref "D5") (pin "1") (pinfunction "A_1") (pintype "passive"))
      (node (ref "R3") (pin "2") (pinfunction "2_2") (pintype "passive"))
    )
    (net (code "69") (name "Net-(D6-K)") (class "Default")
      (node (ref "D6") (pin "2") (pinfunction "K_2") (pintype "passive"))
      (node (ref "Q1") (pin "3") (pinfunction "C_3") (pintype "passive"))
      (node (ref "R7") (pin "2") (pinfunction "2_2") (pintype "passive"))
    )
    (net (code "70") (name "Net-(P1-Pad3)") (class "Default")
      (node (ref "P1") (pin "3") (pinfunction "3_3") (pintype "passive"))
      (node (ref "R5") (pin "2") (pinfunction "2_2") (pintype "passive"))
    )
    (net (code "71") (name "Net-(P1-Pad4)") (class "Default")
      (node (ref "P1") (pin "4") (pinfunction "4_4") (pintype "passive"))
      (node (ref "R4") (pin "2") (pinfunction "2_2") (pintype "passive"))
    )
    (net (code "72") (name "Net-(Q1-B)") (class "Default")
      (node (ref "Q1") (pin "2") (pinfunction "B_2") (pintype "passive"))
      (node (ref "R12") (pin "1") (pinfunction "1_1") (pintype "passive"))
    )
    (net (code "73") (name "Net-(Q2-B)") (class "Default")
      (node (ref "Q2") (pin "2") (pinfunction "B_2") (pintype "passive"))
      (node (ref "R15") (pin "2") (pinfunction "2_2") (pintype "passive"))
    )
    (net (code "74") (name "Net-(Q2-C)") (class "Default")
      (node (ref "Q2") (pin "3") (pinfunction "C_3") (pintype "passive"))
      (node (ref "R17") (pin "2") (pinfunction "2_2") (pintype "passive"))
    )
    (net (code "75") (name "Net-(U1-VDDA)") (class "Default")
      (node (ref "C18") (pin "2") (pinfunction "2_2") (pintype "passive"))
      (node (ref "C19") (pin "2") (pinfunction "2_2") (pintype "passive"))
      (node (ref "R16") (pin "1") (pinfunction "1_1") (pintype "passive"))
      (node (ref "U1") (pin "13") (pinfunction "VDDA_13") (pintype "passive"))
    )
    (net (code "76") (name "Net-(U2-GND)") (class "Default")
      (node (ref "F1") (pin "2") (pinfunction "2_2") (pintype "passive"))
      (node (ref "U2") (pin "5") (pinfunction "GND_5") (pintype "passive"))
    )
    (net (code "77") (name "Net-(U2-VCC)") (class "Default")
      (node (ref "K1") (pin "3") (pinfunction "I/O1_3") (pintype "passive"))
      (node (ref "K1") (pin "4") (pinfunction "I/O2_4") (pintype "passive"))
      (node (ref "U2") (pin "1") (pinfunction "VCC_1") (pintype "passive"))
    )
    (net (code "78") (name "VCC3.3") (class "Default")
      (node (ref "A1") (pin "2") (pinfunction "OUT_2") (pintype "passive"))
      (node (ref "A1") (pin "4") (pinfunction "OUT_4") (pintype "passive"))
      (node (ref "C1") (pin "1") (pinfunction "1_1") (pintype "passive"))
      (node (ref "C13") (pin "1") (pinfunction "1_1") (pintype "passive"))
      (node (ref "C21") (pin "2") (pinfunction "2_2") (pintype "passive"))
      (node (ref "C22") (pin "1") (pinfunction "1_1") (pintype "passive"))
      (node (ref "C4") (pin "1") (pinfunction "1_1") (pintype "passive"))
      (node (ref "C5") (pin "1") (pinfunction "1_1") (pintype "passive"))
      (node (ref "C8") (pin "1") (pinfunction "1_1") (pintype "passive"))
      (node (ref "D1") (pin "1") (pinfunction "A_1") (pintype "passive"))
      (node (ref "J1") (pin "1") (pinfunction "VDD_1") (pintype "passive"))
      (node (ref "J1") (pin "2") (pinfunction "VDD_2") (pintype "passive"))
      (node (ref "P1") (pin "1") (pinfunction "1_1") (pintype "passive"))
      (node (ref "P1") (pin "2") (pinfunction "2_2") (pintype "passive"))
      (node (ref "P7") (pin "1") (pinfunction "1_1") (pintype "passive"))
      (node (ref "P7") (pin "3") (pinfunction "3_3") (pintype "passive"))
      (node (ref "P7") (pin "5") (pinfunction "5_5") (pintype "passive"))
      (node (ref "Q2") (pin "1") (pinfunction "E_1") (pintype "passive"))
      (node (ref "R1") (pin "1") (pinfunction "1_1") (pintype "passive"))
      (node (ref "R10") (pin "1") (pinfunction "1_1") (pintype "passive"))
      (node (ref "R11") (pin "1") (pinfunction "1_1") (pintype "passive"))
      (node (ref "R13") (pin "1") (pinfunction "1_1") (pintype "passive"))
      (node (ref "R16") (pin "2") (pinfunction "2_2") (pintype "passive"))
      (node (ref "R18") (pin "1") (pinfunction "1_1") (pintype "passive"))
      (node (ref "R2") (pin "1") (pinfunction "1_1") (pintype "passive"))
      (node (ref "R3") (pin "1") (pinfunction "1_1") (pintype "passive"))
      (node (ref "R7") (pin "1") (pinfunction "1_1") (pintype "passive"))
      (node (ref "R8") (pin "1") (pinfunction "1_1") (pintype "passive"))
      (node (ref "R9") (pin "2") (pinfunction "2_2") (pintype "passive"))
      (node (ref "U1") (pin "19") (pinfunction "VDD_19") (pintype "passive"))
      (node (ref "U1") (pin "32") (pinfunction "VDD_32") (pintype "passive"))
      (node (ref "U1") (pin "48") (pinfunction "VDD_48") (pintype "passive"))
      (node (ref "U1") (pin "64") (pinfunction "VDD_64") (pintype "passive"))
    )
    (net (code "79") (name "VCC5") (class "Default")
      (node (ref "A1") (pin "3") (pinfunction "IN_3") (pintype "passive"))
      (node (ref "C10") (pin "2") (pinfunction "2_2") (pintype "passive"))
      (node (ref "C11") (pin "16") (pinfunction "VCC_16") (pintype "passive"))
      (node (ref "C12") (pin "2") (pinfunction "2_2") (pintype "passive"))
      (node (ref "C20") (pin "1") (pinfunction "1_1") (pintype "passive"))
      (node (ref "C23") (pin "2") (pinfunction "2_2") (pintype "passive"))
      (node (ref "K1") (pin "2") (pinfunction "TAP1_2") (pintype "passive"))
      (node (ref "K1") (pin "5") (pinfunction "TAP2_5") (pintype "passive"))
      (node (ref "P6") (pin "1") (pinfunction "1_1") (pintype "passive"))
      (node (ref "P6") (pin "3") (pinfunction "3_3") (pintype "passive"))
      (node (ref "P6") (pin "5") (pinfunction "5_5") (pintype "passive"))
    )
    (net (code "80") (name "unconnected-(C11-CTS#-Pad9)") (class "Default")
      (node (ref "C11") (pin "9") (pinfunction "CTS#_9") (pintype "passive"))
    )
    (net (code "81") (name "unconnected-(C11-DCD#-Pad12)") (class "Default")
      (node (ref "C11") (pin "12") (pinfunction "DCD#_12") (pintype "passive"))
    )
    (net (code "82") (name "unconnected-(C11-DSR#-Pad10)") (class "Default")
      (node (ref "C11") (pin "10") (pinfunction "DSR#_10") (pintype "passive"))
    )
    (net (code "83") (name "unconnected-(C11-R232-Pad15)") (class "Default")
      (node (ref "C11") (pin "15") (pinfunction "R232_15") (pintype "passive"))
    )
    (net (code "84") (name "unconnected-(C11-RI#-Pad11)") (class "Default")
      (node (ref "C11") (pin "11") (pinfunction "RI#_11") (pintype "passive"))
    )
    (net (code "85") (name "unconnected-(J1-NC-Pad11)") (class "Default")
      (node (ref "J1") (pin "11") (pinfunction "NC_11") (pintype "passive"))
    )
    (net (code "86") (name "unconnected-(J1-NC-Pad17)") (class "Default")
      (node (ref "J1") (pin "17") (pinfunction "NC_17") (pintype "passive"))
    )
    (net (code "87") (name "unconnected-(J1-NC-Pad19)") (class "Default")
      (node (ref "J1") (pin "19") (pinfunction "NC_19") (pintype "passive"))
    )
    (net (code "88") (name "unconnected-(K1-I{slash}O1-Pad1)") (class "Default")
      (node (ref "K1") (pin "1") (pinfunction "I/O1_1") (pintype "passive"))
    )
    (net (code "89") (name "unconnected-(K1-I{slash}O2-Pad6)") (class "Default")
      (node (ref "K1") (pin "6") (pinfunction "I/O2_6") (pintype "passive"))
    )
    (net (code "90") (name "unconnected-(U2-NC-Pad4)") (class "Default")
      (node (ref "U2") (pin "4") (pinfunction "NC_4") (pintype "passive"))
    )
  )
)
